# FTDI.net
KiCad netlist of a schematic drawn in Altium Designer
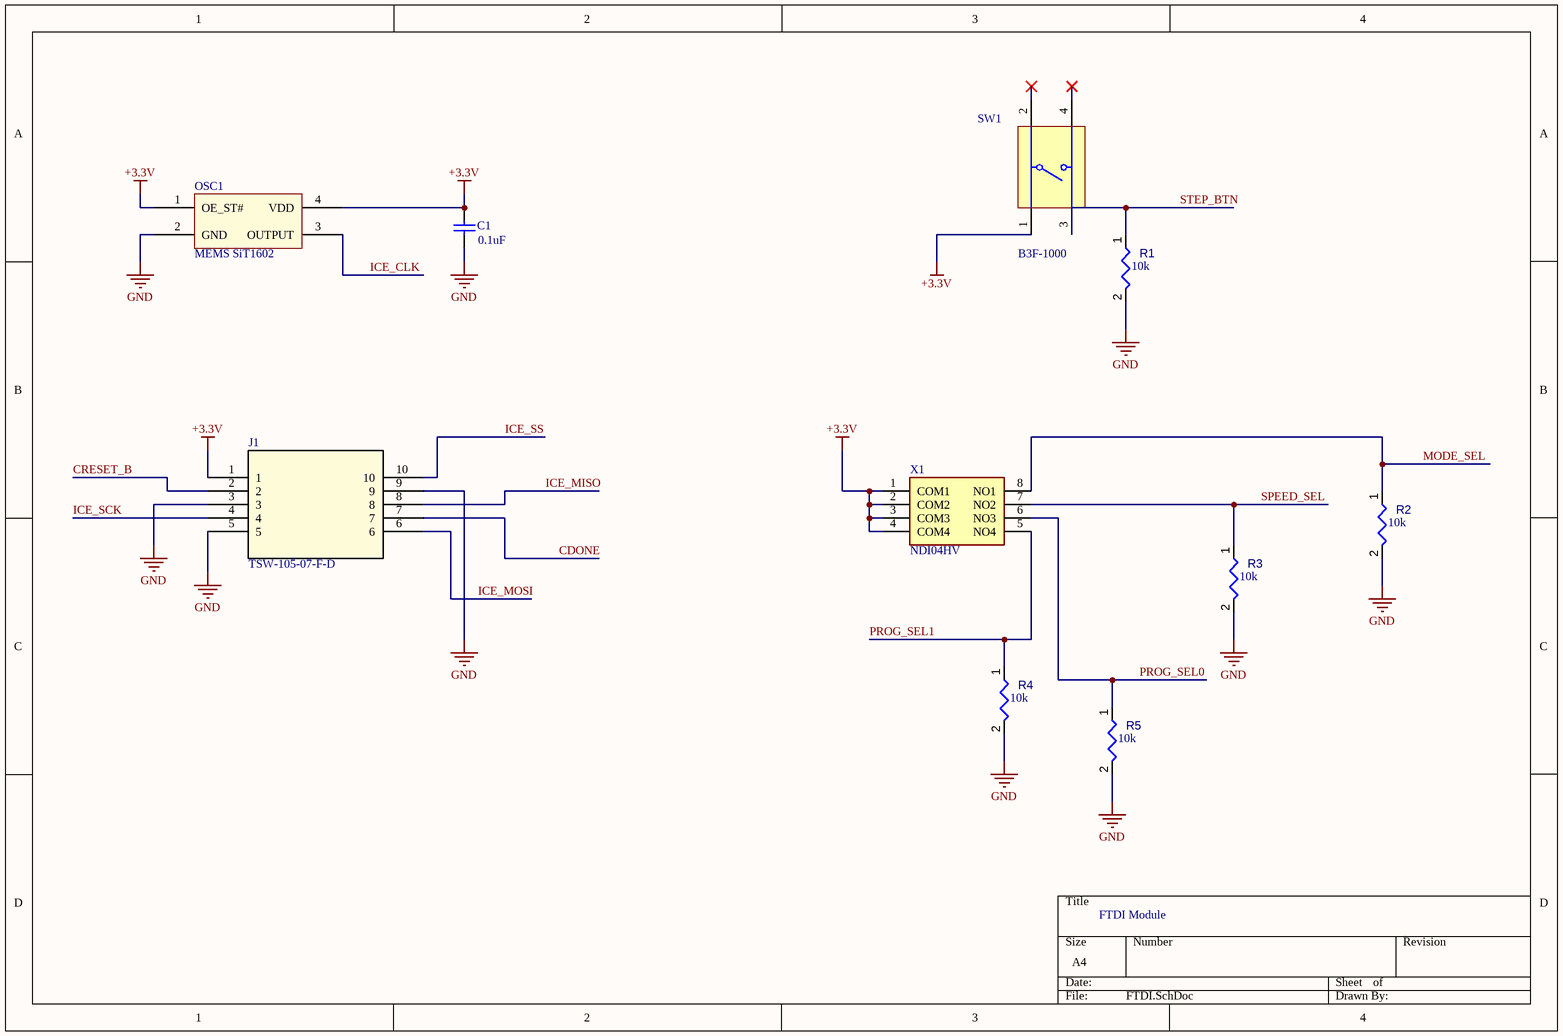
[diagram p0: FTDI.SchDoc]

(export (version "E")
  (design (tool "Eeschema 10.0.6"))
  (components
    (comp (ref "C1")
      (value "0.1uF")
      (footprint "C0402")
      (description "Capacitor (Semiconductor SIM Model)")
      (fields
        (field (name "MANUFACTURER") "Samsung Electro-Mechanics")
        (field (name "MANUFACTURER PART NUMBER") "CL05B104KA5NNNC")
        (field (name "PUBLISHER") "Altium Limited")
      )
      (libsource (lib "Miscellaneous Devices") (part "Cap Semi"))
    )
    (comp (ref "J1")
      (value "TSW-105-07-F-D")
      (footprint "TSW-105-07-G-D_SAI")
      (description "Description")
      (fields (field (name "COPYRIGHT") "Copyright (C) 2025 Ultra Librarian. All rights reserved."))
      (libsource (lib "Talha Khan") (part "TSW-105-07-F-D"))
    )
    (comp (ref "OSC1")
      (value "MEMS SiT1602")
      (footprint "oscMEMS1602")
      (description "MEMS OSC XO 12.0000MHZ LVCMOS")
      (fields
        (field (name "MANUFACTURER") "SiTIME")
        (field (name "MANUFACTURER PART NUMBER") "SIT1602AC-13-33E-12.000000G")
      )
      (libsource (lib "FPGAlib") (part "SIT1602AC-13-33E-12.000000G"))
    )
    (comp (ref "R1")
      (value "10k")
      (footprint "RESC2013X50X35ML15T15")
      (description "Chip Resistor, 10 KOhm, +/- 1%, 125 mW, -55 to 155 degC, 0805 (2012 Metric)")
      (fields (field (name "TOLERANCE") "1%") (field (name "POWER") "125mW"))
      (libsource (lib "Talha Khan") (part "RES-2"))
    )
    (comp (ref "R2")
      (value "10k")
      (footprint "RESC2013X50X35ML15T15")
      (description "Chip Resistor, 10 KOhm, +/- 1%, 125 mW, -55 to 155 degC, 0805 (2012 Metric)")
      (fields (field (name "TOLERANCE") "1%") (field (name "POWER") "125mW"))
      (libsource (lib "Talha Khan") (part "RES-2"))
    )
    (comp (ref "R3")
      (value "10k")
      (footprint "RESC2013X50X35ML15T15")
      (description "Chip Resistor, 10 KOhm, +/- 1%, 125 mW, -55 to 155 degC, 0805 (2012 Metric)")
      (fields (field (name "TOLERANCE") "1%") (field (name "POWER") "125mW"))
      (libsource (lib "Talha Khan") (part "RES-2"))
    )
    (comp (ref "R4")
      (value "10k")
      (footprint "RESC2013X50X35ML15T15")
      (description "Chip Resistor, 10 KOhm, +/- 1%, 125 mW, -55 to 155 degC, 0805 (2012 Metric)")
      (fields (field (name "TOLERANCE") "1%") (field (name "POWER") "125mW"))
      (libsource (lib "Talha Khan") (part "RES-2"))
    )
    (comp (ref "R5")
      (value "10k")
      (footprint "RESC2013X50X35ML15T15")
      (description "Chip Resistor, 10 KOhm, +/- 1%, 125 mW, -55 to 155 degC, 0805 (2012 Metric)")
      (fields (field (name "TOLERANCE") "1%") (field (name "POWER") "125mW"))
      (libsource (lib "Talha Khan") (part "RES-2"))
    )
    (comp (ref "SW1")
      (value "B3F-1000")
      (footprint "OMRON-B3F-1000-4_V")
      (description "Tactile Switch, SPST-NO, 0.05 A, 24 V, -25 to 70 degC, 4-Pin THD, RoHS, Bulk")
      (fields (field (name "MANUFACTURER") "Omron Electronic Components"))
      (libsource (lib "Talha Khan") (part "SW-SPST-4_A"))
    )
    (comp (ref "X1")
      (value "NDI04HV")
      (footprint "NDI04HV")
      (description "Dip Switch SPST 4 Position Through Hole Slide (Standard) Actuator 25mA 24VDC")
      (fields (field (name "MOUSER PART NUMBER") "642-NDI04HV"))
      (libsource (lib "Talha Khan") (part "NDI04HV"))
    )
  )
  (nets
    (net (code "1") (name "+3.3V") (class "Default")
      (node (ref "C1") (pin "2") (pinfunction "2_2") (pintype "passive"))
      (node (ref "J1") (pin "1") (pinfunction "1_1") (pintype "passive"))
      (node (ref "OSC1") (pin "1") (pinfunction "OE_ST#_1") (pintype "passive"))
      (node (ref "OSC1") (pin "4") (pinfunction "VDD_4") (pintype "passive"))
      (node (ref "SW1") (pin "1") (pinfunction "1_1") (pintype "passive"))
      (node (ref "X1") (pin "1") (pinfunction "COM1_1") (pintype "passive"))
      (node (ref "X1") (pin "2") (pinfunction "COM2_2") (pintype "passive"))
      (node (ref "X1") (pin "3") (pinfunction "COM3_3") (pintype "passive"))
      (node (ref "X1") (pin "4") (pinfunction "COM4_4") (pintype "passive"))
    )
    (net (code "2") (name "/CDONE") (class "Default")
      (node (ref "J1") (pin "7") (pinfunction "7_7") (pintype "passive"))
    )
    (net (code "3") (name "/CRESET_B") (class "Default")
      (node (ref "J1") (pin "2") (pinfunction "2_2") (pintype "passive"))
    )
    (net (code "4") (name "/ICE_CLK") (class "Default")
      (node (ref "OSC1") (pin "3") (pinfunction "OUTPUT_3") (pintype "passive"))
    )
    (net (code "5") (name "/ICE_MISO") (class "Default")
      (node (ref "J1") (pin "8") (pinfunction "8_8") (pintype "passive"))
    )
    (net (code "6") (name "/ICE_MOSI") (class "Default")
      (node (ref "J1") (pin "6") (pinfunction "6_6") (pintype "passive"))
    )
    (net (code "7") (name "/ICE_SCK") (class "Default")
      (node (ref "J1") (pin "4") (pinfunction "4_4") (pintype "passive"))
    )
    (net (code "8") (name "/ICE_SS") (class "Default")
      (node (ref "J1") (pin "10") (pinfunction "10_10") (pintype "passive"))
    )
    (net (code "9") (name "/MODE_SEL") (class "Default")
      (node (ref "R2") (pin "1") (pinfunction "1_1") (pintype "passive"))
      (node (ref "X1") (pin "8") (pinfunction "NO1_8") (pintype "passive"))
    )
    (net (code "10") (name "/PROG_SEL0") (class "Default")
      (node (ref "R5") (pin "1") (pinfunction "1_1") (pintype "passive"))
      (node (ref "X1") (pin "6") (pinfunction "NO3_6") (pintype "passive"))
    )
    (net (code "11") (name "/PROG_SEL1") (class "Default")
      (node (ref "R4") (pin "1") (pinfunction "1_1") (pintype "passive"))
      (node (ref "X1") (pin "5") (pinfunction "NO4_5") (pintype "passive"))
    )
    (net (code "12") (name "/SPEED_SEL") (class "Default")
      (node (ref "R3") (pin "1") (pinfunction "1_1") (pintype "passive"))
      (node (ref "X1") (pin "7") (pinfunction "NO2_7") (pintype "passive"))
    )
    (net (code "13") (name "/STEP_BTN") (class "Default")
      (node (ref "R1") (pin "1") (pinfunction "1_1") (pintype "passive"))
      (node (ref "SW1") (pin "3") (pinfunction "3_3") (pintype "passive"))
    )
    (net (code "14") (name "GND") (class "Default")
      (node (ref "C1") (pin "1") (pinfunction "1_1") (pintype "passive"))
      (node (ref "J1") (pin "3") (pinfunction "3_3") (pintype "passive"))
      (node (ref "J1") (pin "5") (pinfunction "5_5") (pintype "passive"))
      (node (ref "J1") (pin "9") (pinfunction "9_9") (pintype "passive"))
      (node (ref "OSC1") (pin "2") (pinfunction "GND_2") (pintype "passive"))
      (node (ref "R1") (pin "2") (pinfunction "2_2") (pintype "passive"))
      (node (ref "R2") (pin "2") (pinfunction "2_2") (pintype "passive"))
      (node (ref "R3") (pin "2") (pinfunction "2_2") (pintype "passive"))
      (node (ref "R4") (pin "2") (pinfunction "2_2") (pintype "passive"))
      (node (ref "R5") (pin "2") (pinfunction "2_2") (pintype "passive"))
    )
    (net (code "15") (name "unconnected-(SW1-Pad2)") (class "Default")
      (node (ref "SW1") (pin "2") (pinfunction "2_2") (pintype "passive+no_connect"))
    )
    (net (code "16") (name "unconnected-(SW1-Pad4)") (class "Default")
      (node (ref "SW1") (pin "4") (pinfunction "4_4") (pintype "passive+no_connect"))
    )
  )
)
